# Encoder_Circuit_1.net
KiCad netlist of a schematic drawn in Altium Designer
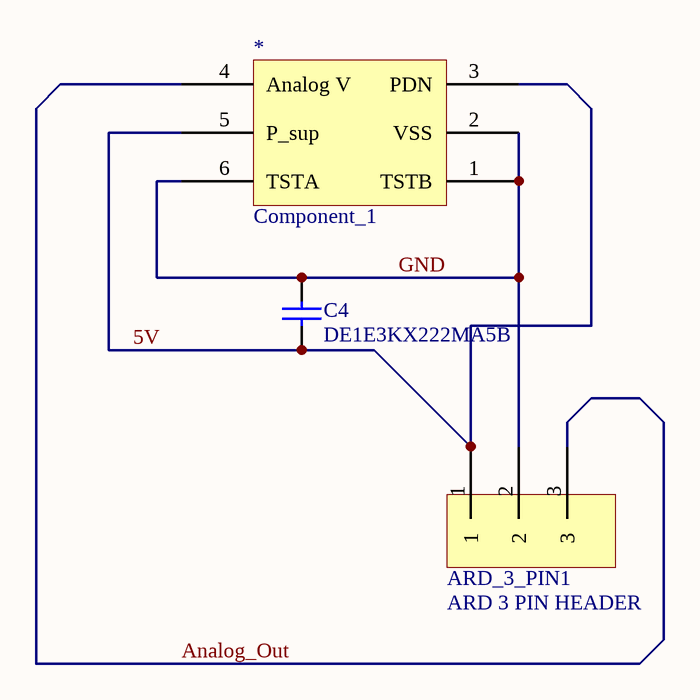
[diagram p0: Encoder Circuit (1).SchDoc]

(export (version "E")
  (design (tool "Eeschema 10.0.6"))
  (components
    (comp (ref "*") (value "Component_1") (libsource (lib "EM3242") (part "Component_1")))
    (comp (ref "ARD_3_PIN1")
      (value "ARD 3 PIN HEADER")
      (footprint "4 PIN HEADER")
      (libsource (lib "ARD_3_PIN_HEADER") (part "ARD_3_PIN?"))
    )
    (comp (ref "C4")
      (value "DE1E3KX222MA5B")
      (footprint "MURA-DE1E3KX222MA5")
      (description "Ceramic Capacitor, 2.2 nF, +/- 20%, 250 V, -25 to 85 degC, 2-Pin THD, RoHS, Bulk")
      (fields (field (name "MANUFACTURER") "Murata"))
      (libsource (lib "Altium Content Vault") (part "CAP-NP-2"))
    )
  )
  (nets
    (net (code "1") (name "/5V") (class "Default")
      (node (ref "*") (pin "3") (pinfunction "PDN_3") (pintype "passive"))
      (node (ref "*") (pin "5") (pinfunction "P_sup_5") (pintype "passive"))
      (node (ref "ARD_3_PIN1") (pin "1") (pinfunction "1_1") (pintype "passive"))
      (node (ref "C4") (pin "1") (pinfunction "1_1") (pintype "passive"))
    )
    (net (code "2") (name "/Analog_Out") (class "Default")
      (node (ref "*") (pin "4") (pinfunction "Analog_V_4") (pintype "passive"))
      (node (ref "ARD_3_PIN1") (pin "3") (pinfunction "3_3") (pintype "passive"))
    )
    (net (code "3") (name "/GND") (class "Default")
      (node (ref "*") (pin "1") (pinfunction "TSTB_1") (pintype "passive"))
      (node (ref "*") (pin "2") (pinfunction "VSS_2") (pintype "passive"))
      (node (ref "*") (pin "6") (pinfunction "TSTA_6") (pintype "passive"))
      (node (ref "ARD_3_PIN1") (pin "2") (pinfunction "2_2") (pintype "passive"))
      (node (ref "C4") (pin "2") (pinfunction "2_2") (pintype "passive"))
    )
  )
)
